# SmartHive_Client.net
KiCad netlist of a schematic drawn in Altium Designer
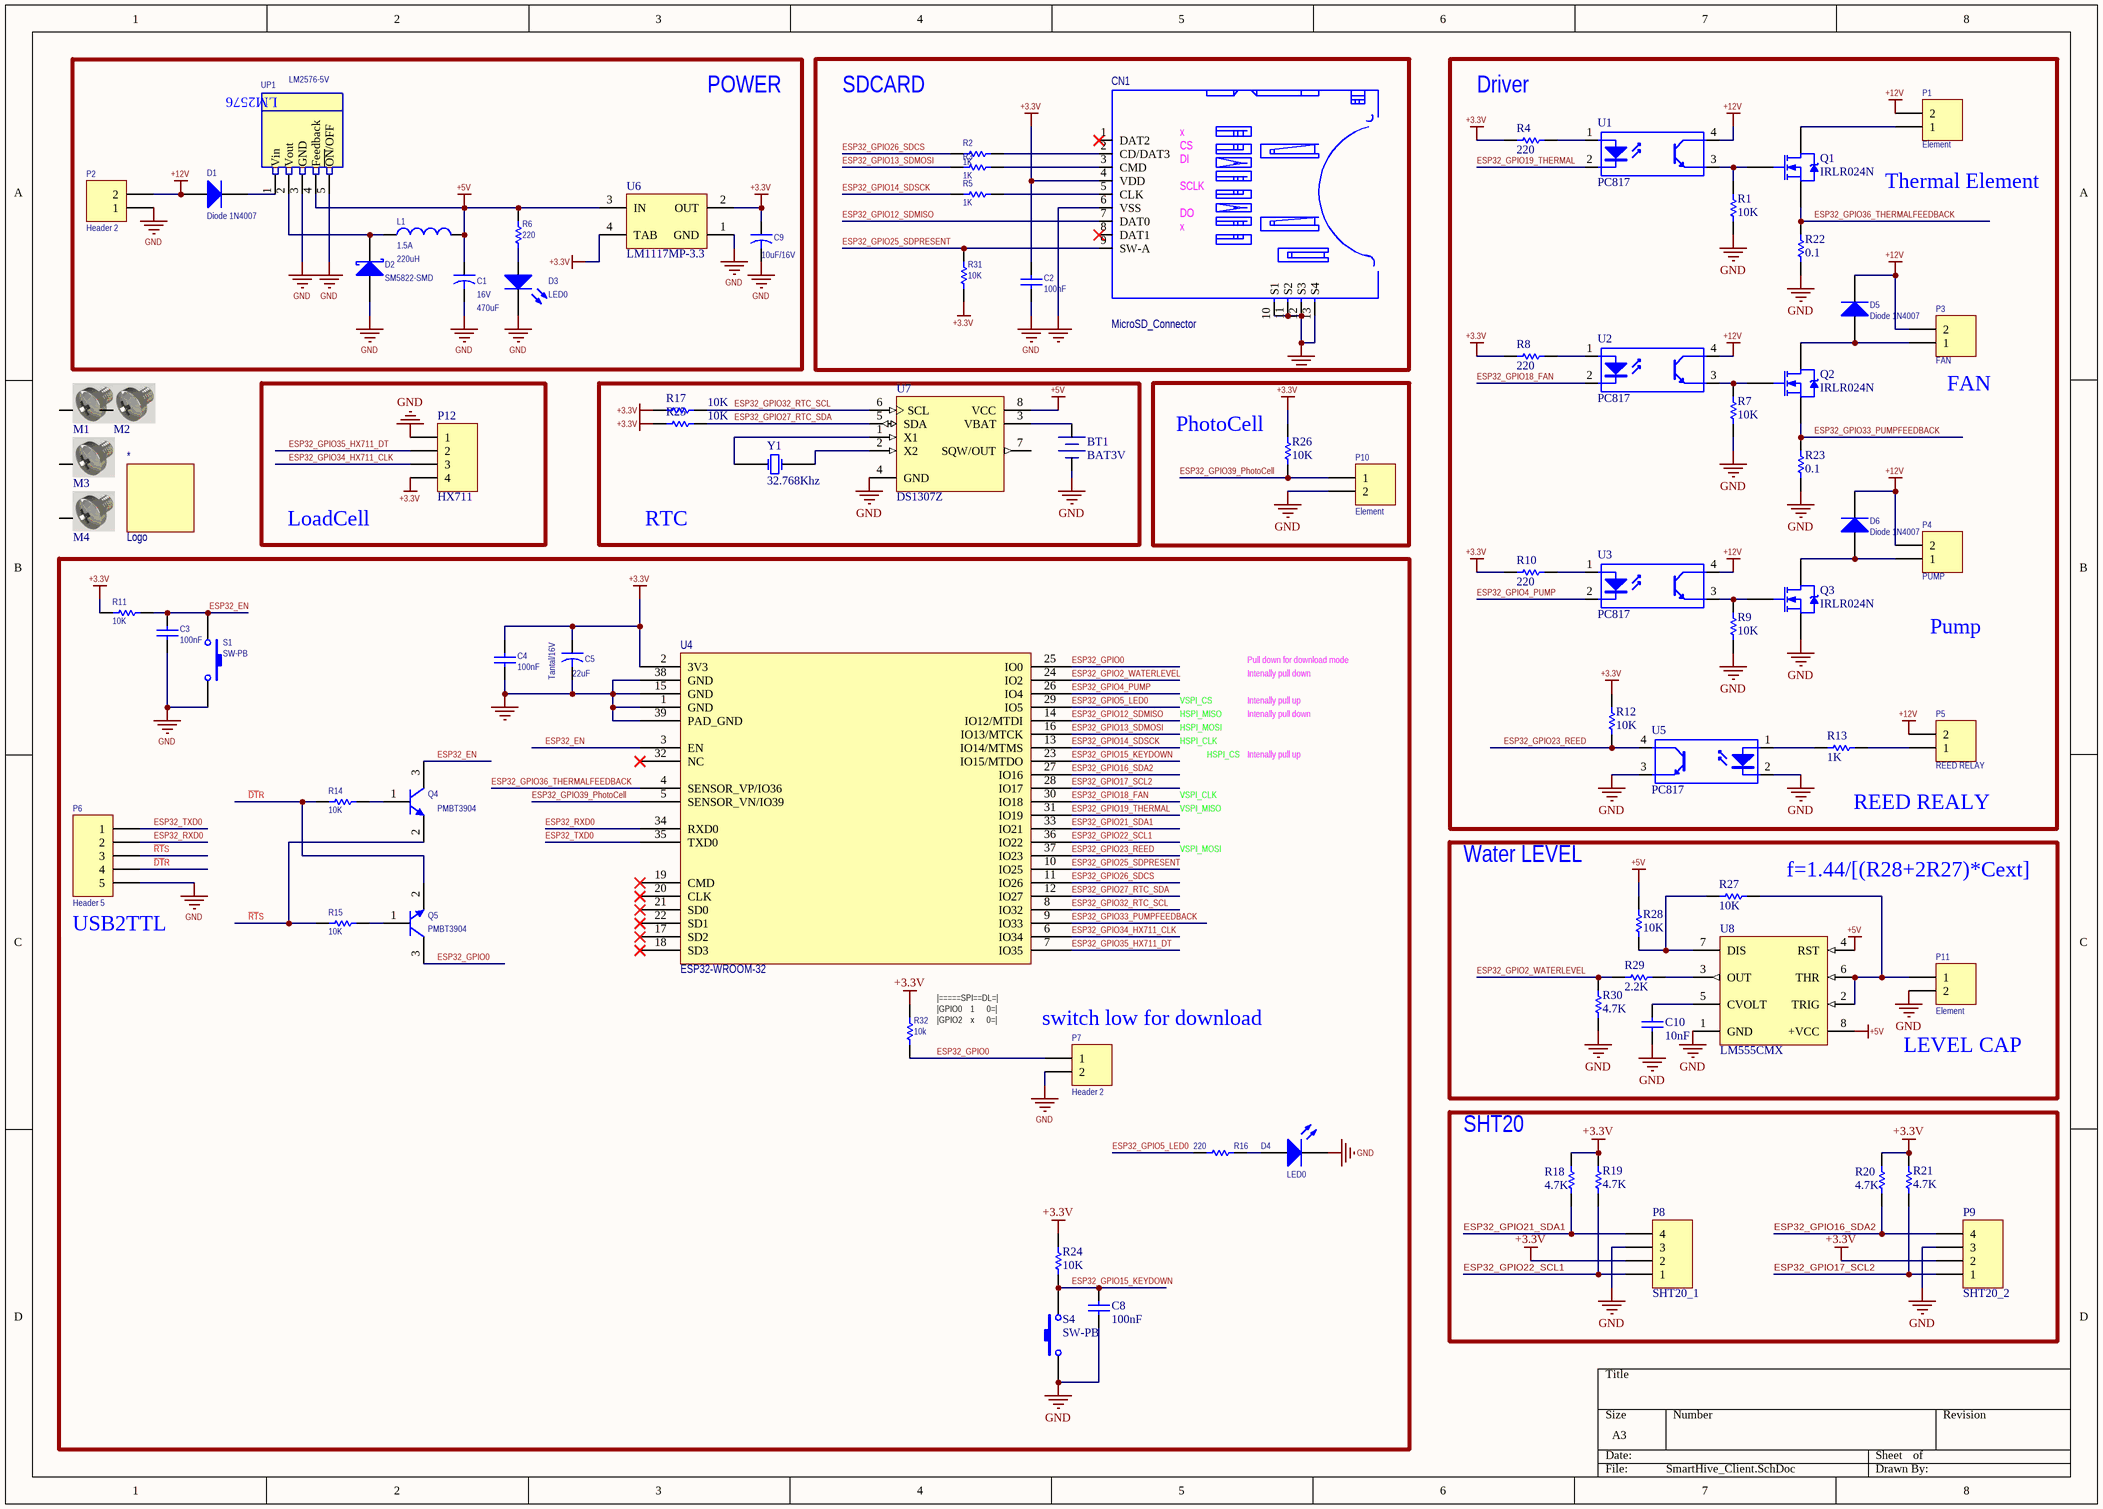
[diagram p0: SmartHive_Client.SchDoc]

(export (version "E")
  (design (tool "Eeschema 10.0.6"))
  (components
    (comp (ref "*") (value "Logo") (footprint "LOGO_PARS_TOP") (libsource (lib "Mofidi3D") (part "Logo")))
    (comp (ref "BT1")
      (value "BAT3V")
      (footprint "BTH2032_DIP")
      (description "Battry Backup")
      (fields (field (name "DESIGNER") "Abbas Basereh"))
      (libsource (lib "Mofidi3D") (part "Battry Backup"))
    )
    (comp (ref "C1")
      (value "16V")
      (footprint "Cap electrolitic radial 8x12-3.5")
      (description "Capacitor")
      (fields (field (name "ALTIUM_VALUE") "470uF") (field (name "PUBLISHER") "Altium Limited"))
      (libsource (lib "Miscellaneous Devices") (part "Cap2"))
    )
    (comp (ref "C2")
      (value "100nF")
      (footprint "CAP0805")
      (description "Capacitor")
      (fields (field (name "PUBLISHER") "Altium Limited"))
      (libsource (lib "Miscellaneous Devices") (part "Cap"))
    )
    (comp (ref "C3")
      (value "100nF")
      (footprint "CAP0805")
      (description "Capacitor")
      (fields (field (name "PUBLISHER") "Altium Limited"))
      (libsource (lib "Miscellaneous Devices") (part "Cap"))
    )
    (comp (ref "C4")
      (value "100nF")
      (footprint "CAP0805")
      (description "Capacitor")
      (fields (field (name "PUBLISHER") "Altium Limited"))
      (libsource (lib "Miscellaneous Devices") (part "Cap"))
    )
    (comp (ref "C5")
      (value "Tantal/16V")
      (footprint "CAP_TANTAL_TYPE_B")
      (description "Capacitor")
      (fields (field (name "ALTIUM_VALUE") "22uF") (field (name "PUBLISHER") "Altium Limited"))
      (libsource (lib "Miscellaneous Devices") (part "Cap2"))
    )
    (comp (ref "C8")
      (value "100nF")
      (footprint "CAP0805")
      (description "Capacitor")
      (fields (field (name "PUBLISHER") "Altium Limited"))
      (libsource (lib "Miscellaneous Devices") (part "Cap"))
    )
    (comp (ref "C9")
      (value "10uF/16V")
      (footprint "Cap electrolitic radial 5x11-2")
      (description "Capacitor")
      (fields (field (name "PUBLISHER") "Altium Limited"))
      (libsource (lib "Miscellaneous Devices") (part "Cap2"))
    )
    (comp (ref "C10")
      (value "10nF")
      (footprint "CAP0805")
      (description "Capacitor")
      (fields (field (name "PUBLISHER") "Altium Limited"))
      (libsource (lib "Miscellaneous Devices") (part "Cap"))
    )
    (comp (ref "CN1")
      (value "MicroSD_Connector")
      (footprint "MICRO_SD_TFP-09-2-12B")
      (libsource (lib "Mofidi3D") (part "MicroSD_Connector"))
    )
    (comp (ref "D1")
      (value "Diode 1N4007")
      (footprint "DO-241AC")
      (description "1 Amp General Purpose Rectifier")
      (fields (field (name "PUBLISHER") "Altium Limited"))
      (libsource (lib "Miscellaneous Devices") (part "Diode 1N4007"))
    )
    (comp (ref "D2")
      (value "SM5822-SMD")
      (footprint "430X270D")
      (description "Schottky Diode")
      (fields (field (name "PUBLISHER") "Altium Limited"))
      (libsource (lib "Miscellaneous Devices") (part "D Schottky"))
    )
    (comp (ref "D3")
      (value "LED0")
      (footprint "LED5MM_GRN")
      (description "Typical INFRARED GaAs LED")
      (fields (field (name "PUBLISHER") "Altium Limited"))
      (libsource (lib "Miscellaneous Devices") (part "LED0"))
    )
    (comp (ref "D4")
      (value "LED0")
      (footprint "LED5MM_BLUE")
      (description "Typical INFRARED GaAs LED")
      (fields (field (name "PUBLISHER") "Altium Limited"))
      (libsource (lib "Miscellaneous Devices") (part "LED0"))
    )
    (comp (ref "D5")
      (value "Diode 1N4007")
      (footprint "DO-241AC")
      (description "1 Amp General Purpose Rectifier")
      (fields (field (name "PUBLISHER") "Altium Limited"))
      (libsource (lib "Miscellaneous Devices") (part "Diode 1N4007"))
    )
    (comp (ref "D6")
      (value "Diode 1N4007")
      (footprint "DO-241AC")
      (description "1 Amp General Purpose Rectifier")
      (fields (field (name "PUBLISHER") "Altium Limited"))
      (libsource (lib "Miscellaneous Devices") (part "Diode 1N4007"))
    )
    (comp (ref "L1")
      (value "1.5A")
      (footprint "Inductor 10x12 (200 mils)")
      (description "Inductor")
      (fields (field (name "ALTIUM_VALUE") "220uH") (field (name "PUBLISHER") "Altium Limited"))
      (libsource (lib "Miscellaneous Devices") (part "Inductor"))
    )
    (comp (ref "M1")
      (value "Screw3mm")
      (footprint "Board Screw 3mm")
      (description "Board Screw With Spacer 3mm")
      (fields (field (name "DESIGNER") "Abbas Basereh"))
      (libsource (lib "Mofidi3D") (part "Board Screw 3mm"))
    )
    (comp (ref "M2")
      (value "Screw3mm")
      (footprint "Board Screw 3mm")
      (description "Board Screw With Spacer 3mm")
      (fields (field (name "DESIGNER") "Abbas Basereh"))
      (libsource (lib "Mofidi3D") (part "Board Screw 3mm"))
    )
    (comp (ref "M3")
      (value "Screw3mm")
      (footprint "Board Screw 3mm")
      (description "Board Screw With Spacer 3mm")
      (fields (field (name "DESIGNER") "Abbas Basereh"))
      (libsource (lib "Mofidi3D") (part "Board Screw 3mm"))
    )
    (comp (ref "M4")
      (value "Screw3mm")
      (footprint "Board Screw 3mm")
      (description "Board Screw With Spacer 3mm")
      (fields (field (name "DESIGNER") "Abbas Basereh"))
      (libsource (lib "Mofidi3D") (part "Board Screw 3mm"))
    )
    (comp (ref "P1")
      (value "Element")
      (footprint "MSTBV 2,5/2-G-5")
      (description "Header, 2-Pin")
      (fields (field (name "PUBLISHER") "Altium Limited"))
      (libsource (lib "") (part "Header 2_2"))
    )
    (comp (ref "P2")
      (value "Header 2")
      (footprint "MSTBV 2,5/2-G-5")
      (description "Header, 2-Pin")
      (fields (field (name "PUBLISHER") "Altium Limited"))
      (libsource (lib "") (part "Header 2_1"))
    )
    (comp (ref "P3")
      (value "FAN")
      (footprint "MSTBV 2,5/2-G-5")
      (description "Header, 2-Pin")
      (fields (field (name "PUBLISHER") "Altium Limited"))
      (libsource (lib "") (part "Header 2_2"))
    )
    (comp (ref "P4")
      (value "PUMP")
      (footprint "MSTBV 2,5/2-G-5")
      (description "Header, 2-Pin")
      (fields (field (name "PUBLISHER") "Altium Limited"))
      (libsource (lib "") (part "Header 2_2"))
    )
    (comp (ref "P5")
      (value "REED RELAY")
      (footprint "MSTBV 2,5/2-G-5")
      (description "Header, 2-Pin")
      (fields (field (name "PUBLISHER") "Altium Limited"))
      (libsource (lib "") (part "Header 2_2"))
    )
    (comp (ref "P6")
      (value "Header 5")
      (footprint "HDR1X5")
      (description "Header, 5-Pin")
      (fields (field (name "PUBLISHER") "Altium Limited"))
      (libsource (lib "Miscellaneous Connectors") (part "Header 5"))
    )
    (comp (ref "P7")
      (value "Header 2")
      (footprint "Jumper Small - 2.54 - Black")
      (description "Header, 2-Pin")
      (fields (field (name "PUBLISHER") "Altium Limited"))
      (libsource (lib "Miscellaneous Connectors") (part "Header 2"))
    )
    (comp (ref "P8")
      (value "SHT20_1")
      (footprint "XH-4PIN")
      (description "Header, 4-Pin")
      (fields (field (name "PUBLISHER") "Altium Limited"))
      (libsource (lib "Miscellaneous Connectors") (part "Header 4"))
    )
    (comp (ref "P9")
      (value "SHT20_2")
      (footprint "XH-4PIN")
      (description "Header, 4-Pin")
      (fields (field (name "PUBLISHER") "Altium Limited"))
      (libsource (lib "Miscellaneous Connectors") (part "Header 4"))
    )
    (comp (ref "P10")
      (value "Element")
      (footprint "DS1070-2-COMCON")
      (description "Header, 2-Pin")
      (fields (field (name "PUBLISHER") "Altium Limited"))
      (libsource (lib "Miscellaneous Connectors") (part "Header 2"))
    )
    (comp (ref "P11")
      (value "Element")
      (footprint "DS1070-2-COMCON")
      (description "Header, 2-Pin")
      (fields (field (name "PUBLISHER") "Altium Limited"))
      (libsource (lib "Miscellaneous Connectors") (part "Header 2"))
    )
    (comp (ref "P12")
      (value "HX711")
      (footprint "HDR1X4")
      (description "Header, 4-Pin")
      (fields (field (name "PUBLISHER") "Altium Limited"))
      (libsource (lib "") (part "Header 4_1"))
    )
    (comp (ref "Q1")
      (value "IRLR024N")
      (footprint "TO252-3M")
      (description "HEXFET Power MOSFET")
      (fields (field (name "PUBLISHER") "Altium Limited"))
      (libsource (lib "IR Discrete MOSFET - Power") (part "IRLR024N"))
    )
    (comp (ref "Q2")
      (value "IRLR024N")
      (footprint "TO252-3M")
      (description "HEXFET Power MOSFET")
      (fields (field (name "PUBLISHER") "Altium Limited"))
      (libsource (lib "IR Discrete MOSFET - Power") (part "IRLR024N"))
    )
    (comp (ref "Q3")
      (value "IRLR024N")
      (footprint "TO252-3M")
      (description "HEXFET Power MOSFET")
      (fields (field (name "PUBLISHER") "Altium Limited"))
      (libsource (lib "IR Discrete MOSFET - Power") (part "IRLR024N"))
    )
    (comp (ref "Q4")
      (value "PMBT3904")
      (footprint "Mofidi3D:SOT23_M")
      (description "NPN Switching Transistor")
      (fields (field (name "PUBLISHER") "Altium Limited"))
      (libsource (lib "Philips Discrete BJT - Low Power") (part "PMBT3904"))
    )
    (comp (ref "Q5")
      (value "PMBT3904")
      (footprint "Mofidi3D:SOT23_M")
      (description "NPN Switching Transistor")
      (fields (field (name "PUBLISHER") "Altium Limited"))
      (libsource (lib "Philips Discrete BJT - Low Power") (part "PMBT3904"))
    )
    (comp (ref "R1")
      (value "10K")
      (footprint "RES0805")
      (description "Resistor")
      (fields (field (name "PUBLISHER") "Altium Limited"))
      (libsource (lib "Miscellaneous Devices") (part "Res1"))
    )
    (comp (ref "R2")
      (value "1K")
      (footprint "RES0805")
      (description "Resistor")
      (fields (field (name "PUBLISHER") "Altium Limited"))
      (libsource (lib "Miscellaneous Devices") (part "Res1"))
    )
    (comp (ref "R3")
      (value "1K")
      (footprint "RES0805")
      (description "Resistor")
      (fields (field (name "PUBLISHER") "Altium Limited"))
      (libsource (lib "Miscellaneous Devices") (part "Res1"))
    )
    (comp (ref "R4")
      (value "220")
      (footprint "RES0805")
      (description "Resistor")
      (fields (field (name "PUBLISHER") "Altium Limited"))
      (libsource (lib "Miscellaneous Devices") (part "Res1"))
    )
    (comp (ref "R5")
      (value "1K")
      (footprint "RES0805")
      (description "Resistor")
      (fields (field (name "PUBLISHER") "Altium Limited"))
      (libsource (lib "Miscellaneous Devices") (part "Res1"))
    )
    (comp (ref "R6")
      (value "220")
      (footprint "RES0805")
      (description "Resistor")
      (fields (field (name "PUBLISHER") "Altium Limited"))
      (libsource (lib "Miscellaneous Devices") (part "Res1"))
    )
    (comp (ref "R7")
      (value "10K")
      (footprint "RES0805")
      (description "Resistor")
      (fields (field (name "PUBLISHER") "Altium Limited"))
      (libsource (lib "Miscellaneous Devices") (part "Res1"))
    )
    (comp (ref "R8")
      (value "220")
      (footprint "RES0805")
      (description "Resistor")
      (fields (field (name "PUBLISHER") "Altium Limited"))
      (libsource (lib "Miscellaneous Devices") (part "Res1"))
    )
    (comp (ref "R9")
      (value "10K")
      (footprint "RES0805")
      (description "Resistor")
      (fields (field (name "PUBLISHER") "Altium Limited"))
      (libsource (lib "Miscellaneous Devices") (part "Res1"))
    )
    (comp (ref "R10")
      (value "220")
      (footprint "RES0805")
      (description "Resistor")
      (fields (field (name "PUBLISHER") "Altium Limited"))
      (libsource (lib "Miscellaneous Devices") (part "Res1"))
    )
    (comp (ref "R11")
      (value "10K")
      (footprint "RES0805")
      (description "Resistor")
      (fields (field (name "PUBLISHER") "Altium Limited"))
      (libsource (lib "Miscellaneous Devices") (part "Res1"))
    )
    (comp (ref "R12")
      (value "10K")
      (footprint "RES0805")
      (description "Resistor")
      (fields (field (name "PUBLISHER") "Altium Limited"))
      (libsource (lib "Miscellaneous Devices") (part "Res1"))
    )
    (comp (ref "R13")
      (value "1K")
      (footprint "RES0805")
      (description "Resistor")
      (fields (field (name "PUBLISHER") "Altium Limited"))
      (libsource (lib "Miscellaneous Devices") (part "Res1"))
    )
    (comp (ref "R14")
      (value "10K")
      (footprint "RES0805")
      (description "Resistor")
      (fields (field (name "PUBLISHER") "Altium Limited"))
      (libsource (lib "Miscellaneous Devices") (part "Res1"))
    )
    (comp (ref "R15")
      (value "10K")
      (footprint "RES0805")
      (description "Resistor")
      (fields (field (name "PUBLISHER") "Altium Limited"))
      (libsource (lib "Miscellaneous Devices") (part "Res1"))
    )
    (comp (ref "R16")
      (value "220")
      (footprint "RES0805")
      (description "Resistor")
      (fields (field (name "PUBLISHER") "Altium Limited"))
      (libsource (lib "Miscellaneous Devices") (part "Res1"))
    )
    (comp (ref "R17")
      (value "10K")
      (footprint "RES0805")
      (description "Resistor")
      (fields (field (name "PUBLISHER") "Altium Limited"))
      (libsource (lib "Miscellaneous Devices") (part "Res1"))
    )
    (comp (ref "R18")
      (value "4.7K")
      (footprint "RES0805")
      (description "Resistor")
      (fields (field (name "PUBLISHER") "Altium Limited"))
      (libsource (lib "Miscellaneous Devices") (part "Res1"))
    )
    (comp (ref "R19")
      (value "4.7K")
      (footprint "RES0805")
      (description "Resistor")
      (fields (field (name "PUBLISHER") "Altium Limited"))
      (libsource (lib "Miscellaneous Devices") (part "Res1"))
    )
    (comp (ref "R20")
      (value "4.7K")
      (footprint "RES0805")
      (description "Resistor")
      (fields (field (name "PUBLISHER") "Altium Limited"))
      (libsource (lib "Miscellaneous Devices") (part "Res1"))
    )
    (comp (ref "R21")
      (value "4.7K")
      (footprint "RES0805")
      (description "Resistor")
      (fields (field (name "PUBLISHER") "Altium Limited"))
      (libsource (lib "Miscellaneous Devices") (part "Res1"))
    )
    (comp (ref "R22")
      (value "0.1")
      (footprint "RES2512")
      (description "Size:2512,1%")
      (fields (field (name "PUBLISHER") "Altium Limited"))
      (libsource (lib "Miscellaneous Devices") (part "Res1"))
    )
    (comp (ref "R23")
      (value "0.1")
      (footprint "RES2512")
      (description "Size:2512,1%")
      (fields (field (name "PUBLISHER") "Altium Limited"))
      (libsource (lib "Miscellaneous Devices") (part "Res1"))
    )
    (comp (ref "R24")
      (value "10K")
      (footprint "RES0805")
      (description "Resistor")
      (fields (field (name "PUBLISHER") "Altium Limited"))
      (libsource (lib "Miscellaneous Devices") (part "Res1"))
    )
    (comp (ref "R25")
      (value "10K")
      (footprint "RES0805")
      (description "Resistor")
      (fields (field (name "PUBLISHER") "Altium Limited"))
      (libsource (lib "Miscellaneous Devices") (part "Res1"))
    )
    (comp (ref "R26")
      (value "10K")
      (footprint "RES0805")
      (description "Resistor")
      (fields (field (name "PUBLISHER") "Altium Limited"))
      (libsource (lib "Miscellaneous Devices") (part "Res1"))
    )
    (comp (ref "R27")
      (value "10K")
      (footprint "RES0805")
      (description "Resistor")
      (fields (field (name "PUBLISHER") "Altium Limited"))
      (libsource (lib "Miscellaneous Devices") (part "Res1"))
    )
    (comp (ref "R28")
      (value "10K")
      (footprint "RES0805")
      (description "Resistor")
      (fields (field (name "PUBLISHER") "Altium Limited"))
      (libsource (lib "Miscellaneous Devices") (part "Res1"))
    )
    (comp (ref "R29")
      (value "2.2K")
      (footprint "RES0805")
      (description "Resistor")
      (fields (field (name "PUBLISHER") "Altium Limited"))
      (libsource (lib "Miscellaneous Devices") (part "Res1"))
    )
    (comp (ref "R30")
      (value "4.7K")
      (footprint "RES0805")
      (description "Resistor")
      (fields (field (name "PUBLISHER") "Altium Limited"))
      (libsource (lib "Miscellaneous Devices") (part "Res1"))
    )
    (comp (ref "R31")
      (value "10K")
      (footprint "RES0805")
      (description "Resistor")
      (fields (field (name "PUBLISHER") "Altium Limited"))
      (libsource (lib "Miscellaneous Devices") (part "Res1"))
    )
    (comp (ref "R32")
      (value "10k")
      (footprint "RES0805")
      (description "Resistor")
      (fields (field (name "PUBLISHER") "Altium Limited"))
      (libsource (lib "Miscellaneous Devices") (part "Res1"))
    )
    (comp (ref "S1")
      (value "SW-PB")
      (footprint "SW-2PIN-SMD")
      (description "Switch")
      (fields (field (name "PUBLISHER") "Altium Limited"))
      (libsource (lib "Miscellaneous Devices") (part "SW-PB"))
    )
    (comp (ref "S4")
      (value "SW-PB")
      (footprint "SW-4PIN")
      (description "Switch")
      (fields (field (name "PUBLISHER") "Altium Limited"))
      (libsource (lib "Miscellaneous Devices") (part "SW-PB"))
    )
    (comp (ref "U1")
      (value "PC817")
      (footprint "DIP_4")
      (description "4-Pin Phototransistor Optocoupler")
      (fields (field (name "PUBLISHER") "Altium Limited"))
      (libsource (lib "Miscellaneous Devices") (part "Optoisolator1"))
    )
    (comp (ref "U2")
      (value "PC817")
      (footprint "DIP_4")
      (description "4-Pin Phototransistor Optocoupler")
      (fields (field (name "PUBLISHER") "Altium Limited"))
      (libsource (lib "Miscellaneous Devices") (part "Optoisolator1"))
    )
    (comp (ref "U3")
      (value "PC817")
      (footprint "DIP_4")
      (description "4-Pin Phototransistor Optocoupler")
      (fields (field (name "PUBLISHER") "Altium Limited"))
      (libsource (lib "Miscellaneous Devices") (part "Optoisolator1"))
    )
    (comp (ref "U4")
      (value "ESP32-WROOM-32")
      (footprint "ESP32-WROOM-32D")
      (description "ESP32  a single chip 2.4 GHz Wi-Fi and Bluetooth combo chip")
      (libsource (lib "Mofidi3D") (part "ESP32-WROOM-32"))
    )
    (comp (ref "U5")
      (value "PC817")
      (footprint "DIP_4")
      (description "4-Pin Phototransistor Optocoupler")
      (fields (field (name "PUBLISHER") "Altium Limited"))
      (libsource (lib "Miscellaneous Devices") (part "Optoisolator1"))
    )
    (comp (ref "U6")
      (value "LM1117MP-3.3")
      (footprint "SOT223_4")
      (description "800mA Low-Dropout Linear Regulator, 4-pin SOT-223")
      (fields
        (field (name "MANUFACTURER") "National Semiconductor")
        (field (name "PUBLISHER") "Altium Limited")
      )
      (libsource (lib "NSC LDO") (part "LM1117MP-3.3"))
    )
    (comp (ref "U7")
      (value "DS1307Z")
      (footprint "SO-8N")
      (description "64 X 8 Serial Real-Time Clock")
      (fields (field (name "PUBLISHER") "Altium Limited"))
      (libsource (lib "Dallas Peripheral Real Time Clock") (part "DS1307Z"))
    )
    (comp (ref "U8")
      (value "LM555CMX")
      (footprint "SO-8N")
      (description "Timer, 8-pin Narrow SOIC")
      (fields
        (field (name "MANUFACTURER") "National Semiconductor")
        (field (name "PUBLISHER") "Altium Limited")
      )
      (libsource (lib "NSC Analog") (part "LM555CMX"))
    )
    (comp (ref "UP1")
      (value "LM2576-5V")
      (footprint "TO-220_5 with heatsink HS sot32")
      (description "3.3V, 3A variable output step-down switching voltage regulator")
      (fields (field (name "DESIGNER") "Abbas Basereh"))
      (libsource (lib "Mofidi3D") (part "LM2576-Adj"))
    )
    (comp (ref "Y1")
      (value "32.768Khz")
      (footprint "Crystal_NC308")
      (description "XTAL Crystal")
      (fields (field (name "DESIGNER") "ABBAS BASEREH"))
      (libsource (lib "Mofidi3D") (part "XTAL_Crystal"))
    )
  )
  (nets
    (net (code "1") (name "+3.3V") (class "Default")
      (node (ref "C2") (pin "2") (pinfunction "2_2") (pintype "passive"))
      (node (ref "C4") (pin "2") (pinfunction "2_2") (pintype "passive"))
      (node (ref "C5") (pin "1") (pinfunction "1_1") (pintype "passive"))
      (node (ref "C9") (pin "1") (pinfunction "1_1") (pintype "passive"))
      (node (ref "CN1") (pin "4") (pinfunction "VDD_4") (pintype "passive"))
      (node (ref "P12") (pin "4") (pinfunction "4_4") (pintype "passive"))
      (node (ref "P8") (pin "2") (pinfunction "2_2") (pintype "passive"))
      (node (ref "P9") (pin "2") (pinfunction "2_2") (pintype "passive"))
      (node (ref "R10") (pin "1") (pinfunction "1_1") (pintype "passive"))
      (node (ref "R11") (pin "2") (pinfunction "2_2") (pintype "passive"))
      (node (ref "R12") (pin "2") (pinfunction "2_2") (pintype "passive"))
      (node (ref "R17") (pin "2") (pinfunction "2_2") (pintype "passive"))
      (node (ref "R18") (pin "2") (pinfunction "2_2") (pintype "passive"))
      (node (ref "R19") (pin "2") (pinfunction "2_2") (pintype "passive"))
      (node (ref "R20") (pin "2") (pinfunction "2_2") (pintype "passive"))
      (node (ref "R21") (pin "2") (pinfunction "2_2") (pintype "passive"))
      (node (ref "R24") (pin "2") (pinfunction "2_2") (pintype "passive"))
      (node (ref "R25") (pin "2") (pinfunction "2_2") (pintype "passive"))
      (node (ref "R26") (pin "2") (pinfunction "2_2") (pintype "passive"))
      (node (ref "R31") (pin "2") (pinfunction "2_2") (pintype "passive"))
      (node (ref "R32") (pin "2") (pinfunction "2_2") (pintype "passive"))
      (node (ref "R4") (pin "1") (pinfunction "1_1") (pintype "passive"))
      (node (ref "R8") (pin "1") (pinfunction "1_1") (pintype "passive"))
      (node (ref "U4") (pin "2") (pinfunction "3V3_2") (pintype "power_in"))
      (node (ref "U6") (pin "2") (pinfunction "OUT_2") (pintype "power_in"))
      (node (ref "U6") (pin "4") (pinfunction "TAB_4") (pintype "power_in"))
    )
    (net (code "2") (name "+5V") (class "Default")
      (node (ref "C1") (pin "1") (pinfunction "1_1") (pintype "passive"))
      (node (ref "L1") (pin "2") (pinfunction "2_2") (pintype "passive"))
      (node (ref "R28") (pin "2") (pinfunction "2_2") (pintype "passive"))
      (node (ref "R6") (pin "2") (pinfunction "2_2") (pintype "passive"))
      (node (ref "U6") (pin "3") (pinfunction "IN_3") (pintype "power_in"))
      (node (ref "U7") (pin "8") (pinfunction "VCC_8") (pintype "power_in"))
      (node (ref "U8") (pin "4") (pinfunction "RST_4") (pintype "input"))
      (node (ref "U8") (pin "8") (pinfunction "+VCC_8") (pintype "power_in"))
      (node (ref "UP1") (pin "4") (pinfunction "Feedback_4") (pintype "passive"))
    )
    (net (code "3") (name "+12V") (class "Default")
      (node (ref "D1") (pin "1") (pinfunction "A_1") (pintype "passive"))
      (node (ref "D5") (pin "2") (pinfunction "K_2") (pintype "passive"))
      (node (ref "D6") (pin "2") (pinfunction "K_2") (pintype "passive"))
      (node (ref "P1") (pin "2") (pinfunction "2_2") (pintype "passive"))
      (node (ref "P2") (pin "2") (pinfunction "2_2") (pintype "passive"))
      (node (ref "P3") (pin "2") (pinfunction "2_2") (pintype "passive"))
      (node (ref "P4") (pin "2") (pinfunction "2_2") (pintype "passive"))
      (node (ref "P5") (pin "2") (pinfunction "2_2") (pintype "passive"))
      (node (ref "U1") (pin "4") (pinfunction "C_4") (pintype "passive"))
      (node (ref "U2") (pin "4") (pinfunction "C_4") (pintype "passive"))
      (node (ref "U3") (pin "4") (pinfunction "C_4") (pintype "passive"))
    )
    (net (code "4") (name "/ESP32_EN") (class "Default")
      (node (ref "C3") (pin "2") (pinfunction "2_2") (pintype "passive"))
      (node (ref "Q4") (pin "3") (pinfunction "C_3") (pintype "passive"))
      (node (ref "R11") (pin "1") (pinfunction "1_1") (pintype "passive"))
      (node (ref "S1") (pin "1") (pinfunction "1_1") (pintype "passive"))
      (node (ref "U4") (pin "3") (pinfunction "EN_3") (pintype "passive"))
    )
    (net (code "5") (name "/ESP32_GPIO0") (class "Default")
      (node (ref "P7") (pin "1") (pinfunction "1_1") (pintype "passive"))
      (node (ref "Q5") (pin "3") (pinfunction "C_3") (pintype "passive"))
      (node (ref "R32") (pin "1") (pinfunction "1_1") (pintype "passive"))
      (node (ref "U4") (pin "25") (pinfunction "IO0_25") (pintype "passive"))
    )
    (net (code "6") (name "/ESP32_GPIO2_WATERLEVEL") (class "Default")
      (node (ref "R29") (pin "2") (pinfunction "2_2") (pintype "passive"))
      (node (ref "R30") (pin "2") (pinfunction "2_2") (pintype "passive"))
      (node (ref "U4") (pin "24") (pinfunction "IO2_24") (pintype "passive"))
    )
    (net (code "7") (name "/ESP32_GPIO4_PUMP") (class "Default")
      (node (ref "U3") (pin "2") (pinfunction "K_2") (pintype "passive"))
      (node (ref "U4") (pin "26") (pinfunction "IO4_26") (pintype "passive"))
    )
    (net (code "8") (name "/ESP32_GPIO5_LED0") (class "Default")
      (node (ref "R16") (pin "1") (pinfunction "1_1") (pintype "passive"))
      (node (ref "U4") (pin "29") (pinfunction "IO5_29") (pintype "passive"))
    )
    (net (code "9") (name "/ESP32_GPIO12_SDMISO") (class "Default")
      (node (ref "CN1") (pin "7") (pinfunction "DAT0_7") (pintype "passive"))
      (node (ref "U4") (pin "14") (pinfunction "IO12/MTDI_14") (pintype "passive"))
    )
    (net (code "10") (name "/ESP32_GPIO13_SDMOSI") (class "Default")
      (node (ref "R3") (pin "2") (pinfunction "2_2") (pintype "passive"))
      (node (ref "U4") (pin "16") (pinfunction "IO13/MTCK_16") (pintype "passive"))
    )
    (net (code "11") (name "/ESP32_GPIO14_SDSCK") (class "Default")
      (node (ref "R5") (pin "2") (pinfunction "2_2") (pintype "passive"))
      (node (ref "U4") (pin "13") (pinfunction "IO14/MTMS_13") (pintype "passive"))
    )
    (net (code "12") (name "/ESP32_GPIO15_KEYDOWN") (class "Default")
      (node (ref "C8") (pin "2") (pinfunction "2_2") (pintype "passive"))
      (node (ref "R24") (pin "1") (pinfunction "1_1") (pintype "passive"))
      (node (ref "S4") (pin "1") (pinfunction "1_1") (pintype "passive"))
      (node (ref "U4") (pin "23") (pinfunction "IO15/MTDO_23") (pintype "passive"))
    )
    (net (code "13") (name "/ESP32_GPIO16_SDA2") (class "Default")
      (node (ref "P9") (pin "4") (pinfunction "4_4") (pintype "passive"))
      (node (ref "R20") (pin "1") (pinfunction "1_1") (pintype "passive"))
      (node (ref "U4") (pin "27") (pinfunction "IO16_27") (pintype "passive"))
    )
    (net (code "14") (name "/ESP32_GPIO17_SCL2") (class "Default")
      (node (ref "P9") (pin "1") (pinfunction "1_1") (pintype "passive"))
      (node (ref "R21") (pin "1") (pinfunction "1_1") (pintype "passive"))
      (node (ref "U4") (pin "28") (pinfunction "IO17_28") (pintype "passive"))
    )
    (net (code "15") (name "/ESP32_GPIO18_FAN") (class "Default")
      (node (ref "U2") (pin "2") (pinfunction "K_2") (pintype "passive"))
      (node (ref "U4") (pin "30") (pinfunction "IO18_30") (pintype "passive"))
    )
    (net (code "16") (name "/ESP32_GPIO19_THERMAL") (class "Default")
      (node (ref "U1") (pin "2") (pinfunction "K_2") (pintype "passive"))
      (node (ref "U4") (pin "31") (pinfunction "IO19_31") (pintype "passive"))
    )
    (net (code "17") (name "/ESP32_GPIO21_SDA1") (class "Default")
      (node (ref "P8") (pin "4") (pinfunction "4_4") (pintype "passive"))
      (node (ref "R18") (pin "1") (pinfunction "1_1") (pintype "passive"))
      (node (ref "U4") (pin "33") (pinfunction "IO21_33") (pintype "passive"))
    )
    (net (code "18") (name "/ESP32_GPIO22_SCL1") (class "Default")
      (node (ref "P8") (pin "1") (pinfunction "1_1") (pintype "passive"))
      (node (ref "R19") (pin "1") (pinfunction "1_1") (pintype "passive"))
      (node (ref "U4") (pin "36") (pinfunction "IO22_36") (pintype "passive"))
    )
    (net (code "19") (name "/ESP32_GPIO23_REED") (class "Default")
      (node (ref "R12") (pin "1") (pinfunction "1_1") (pintype "passive"))
      (node (ref "U4") (pin "37") (pinfunction "IO23_37") (pintype "passive"))
      (node (ref "U5") (pin "4") (pinfunction "C_4") (pintype "passive"))
    )
    (net (code "20") (name "/ESP32_GPIO25_SDPRESENT") (class "Default")
      (node (ref "CN1") (pin "9") (pinfunction "SW-A_9") (pintype "passive"))
      (node (ref "R31") (pin "1") (pinfunction "1_1") (pintype "passive"))
      (node (ref "U4") (pin "10") (pinfunction "IO25_10") (pintype "passive"))
    )
    (net (code "21") (name "/ESP32_GPIO26_SDCS") (class "Default")
      (node (ref "R2") (pin "2") (pinfunction "2_2") (pintype "passive"))
      (node (ref "U4") (pin "11") (pinfunction "IO26_11") (pintype "passive"))
    )
    (net (code "22") (name "/ESP32_GPIO27_RTC_SDA") (class "Default")
      (node (ref "R25") (pin "1") (pinfunction "1_1") (pintype "passive"))
      (node (ref "U4") (pin "12") (pinfunction "IO27_12") (pintype "passive"))
      (node (ref "U7") (pin "5") (pinfunction "SDA_5") (pintype "bidirectional"))
    )
    (net (code "23") (name "/ESP32_GPIO32_RTC_SCL") (class "Default")
      (node (ref "R17") (pin "1") (pinfunction "1_1") (pintype "passive"))
      (node (ref "U4") (pin "8") (pinfunction "IO32_8") (pintype "passive"))
      (node (ref "U7") (pin "6") (pinfunction "SCL_6") (pintype "input"))
    )
    (net (code "24") (name "/ESP32_GPIO33_PUMPFEEDBACK") (class "Default")
      (node (ref "Q2") (pin "3") (pinfunction "S_3") (pintype "passive"))
      (node (ref "R23") (pin "2") (pinfunction "2_2") (pintype "passive"))
      (node (ref "U4") (pin "9") (pinfunction "IO33_9") (pintype "passive"))
    )
    (net (code "25") (name "/ESP32_GPIO34_HX711_CLK") (class "Default")
      (node (ref "P12") (pin "3") (pinfunction "3_3") (pintype "passive"))
      (node (ref "U4") (pin "6") (pinfunction "IO34_6") (pintype "passive"))
    )
    (net (code "26") (name "/ESP32_GPIO35_HX711_DT") (class "Default")
      (node (ref "P12") (pin "2") (pinfunction "2_2") (pintype "passive"))
      (node (ref "U4") (pin "7") (pinfunction "IO35_7") (pintype "passive"))
    )
    (net (code "27") (name "/ESP32_GPIO36_THERMALFEEDBACK") (class "Default")
      (node (ref "Q1") (pin "3") (pinfunction "S_3") (pintype "passive"))
      (node (ref "R22") (pin "2") (pinfunction "2_2") (pintype "passive"))
      (node (ref "U4") (pin "4") (pinfunction "SENSOR_VP/IO36_4") (pintype "passive"))
    )
    (net (code "28") (name "/ESP32_GPIO39_PhotoCell") (class "Default")
      (node (ref "P10") (pin "1") (pinfunction "1_1") (pintype "passive"))
      (node (ref "R26") (pin "1") (pinfunction "1_1") (pintype "passive"))
      (node (ref "U4") (pin "5") (pinfunction "SENSOR_VN/IO39_5") (pintype "passive"))
    )
    (net (code "29") (name "/ESP32_RXD0") (class "Default")
      (node (ref "P6") (pin "2") (pinfunction "2_2") (pintype "passive"))
      (node (ref "U4") (pin "34") (pinfunction "RXD0_34") (pintype "passive"))
    )
    (net (code "30") (name "/ESP32_TXD0") (class "Default")
      (node (ref "P6") (pin "1") (pinfunction "1_1") (pintype "passive"))
      (node (ref "U4") (pin "35") (pinfunction "TXD0_35") (pintype "passive"))
    )
    (net (code "31") (name "/~{DT}R") (class "Default")
      (node (ref "P6") (pin "4") (pinfunction "4_4") (pintype "passive"))
      (node (ref "Q5") (pin "2") (pinfunction "E_2") (pintype "passive"))
      (node (ref "R14") (pin "2") (pinfunction "2_2") (pintype "passive"))
    )
    (net (code "32") (name "/~{RT}S") (class "Default")
      (node (ref "P6") (pin "3") (pinfunction "3_3") (pintype "passive"))
      (node (ref "Q4") (pin "2") (pinfunction "E_2") (pintype "passive"))
      (node (ref "R15") (pin "2") (pinfunction "2_2") (pintype "passive"))
    )
    (net (code "33") (name "GND") (class "Default")
      (node (ref "BT1") (pin "2") (pinfunction "-_2") (pintype "passive"))
      (node (ref "C1") (pin "2") (pinfunction "2_2") (pintype "passive"))
      (node (ref "C10") (pin "1") (pinfunction "1_1") (pintype "passive"))
      (node (ref "C2") (pin "1") (pinfunction "1_1") (pintype "passive"))
      (node (ref "C3") (pin "1") (pinfunction "1_1") (pintype "passive"))
      (node (ref "C4") (pin "1") (pinfunction "1_1") (pintype "passive"))
      (node (ref "C5") (pin "2") (pinfunction "2_2") (pintype "passive"))
      (node (ref "C8") (pin "1") (pinfunction "1_1") (pintype "passive"))
      (node (ref "C9") (pin "2") (pinfunction "2_2") (pintype "passive"))
      (node (ref "CN1") (pin "10") (pinfunction "S1_10") (pintype "passive"))
      (node (ref "CN1") (pin "11") (pinfunction "S2_11") (pintype "passive"))
      (node (ref "CN1") (pin "12") (pinfunction "S3_12") (pintype "passive"))
      (node (ref "CN1") (pin "13") (pinfunction "S4_13") (pintype "passive"))
      (node (ref "CN1") (pin "6") (pinfunction "VSS_6") (pintype "passive"))
      (node (ref "D2") (pin "1") (pinfunction "A_1") (pintype "passive"))
      (node (ref "D3") (pin "2") (pinfunction "K_2") (pintype "passive"))
      (node (ref "D4") (pin "2") (pinfunction "K_2") (pintype "passive"))
      (node (ref "P10") (pin "2") (pinfunction "2_2") (pintype "passive"))
      (node (ref "P11") (pin "2") (pinfunction "2_2") (pintype "passive"))
      (node (ref "P12") (pin "1") (pinfunction "1_1") (pintype "passive"))
      (node (ref "P2") (pin "1") (pinfunction "1_1") (pintype "passive"))
      (node (ref "P6") (pin "5") (pinfunction "5_5") (pintype "passive"))
      (node (ref "P7") (pin "2") (pinfunction "2_2") (pintype "passive"))
      (node (ref "P8") (pin "3") (pinfunction "3_3") (pintype "passive"))
      (node (ref "P9") (pin "3") (pinfunction "3_3") (pintype "passive"))
      (node (ref "Q3") (pin "3") (pinfunction "S_3") (pintype "passive"))
      (node (ref "R1") (pin "1") (pinfunction "1_1") (pintype "passive"))
      (node (ref "R22") (pin "1") (pinfunction "1_1") (pintype "passive"))
      (node (ref "R23") (pin "1") (pinfunction "1_1") (pintype "passive"))
      (node (ref "R30") (pin "1") (pinfunction "1_1") (pintype "passive"))
      (node (ref "R7") (pin "1") (pinfunction "1_1") (pintype "passive"))
      (node (ref "R9") (pin "1") (pinfunction "1_1") (pintype "passive"))
      (node (ref "S1") (pin "2") (pinfunction "2_2") (pintype "passive"))
      (node (ref "S4") (pin "2") (pinfunction "2_2") (pintype "passive"))
      (node (ref "U4") (pin "1") (pinfunction "GND_1") (pintype "power_in"))
      (node (ref "U4") (pin "15") (pinfunction "GND_15") (pintype "power_in"))
      (node (ref "U4") (pin "38") (pinfunction "GND_38") (pintype "power_in"))
      (node (ref "U4") (pin "39") (pinfunction "PAD_GND_39") (pintype "passive"))
      (node (ref "U5") (pin "2") (pinfunction "K_2") (pintype "passive"))
      (node (ref "U5") (pin "3") (pinfunction "E_3") (pintype "passive"))
      (node (ref "U6") (pin "1") (pinfunction "GND_1") (pintype "power_in"))
      (node (ref "U7") (pin "4") (pinfunction "GND_4") (pintype "power_in"))
      (node (ref "U8") (pin "1") (pinfunction "GND_1") (pintype "power_in"))
      (node (ref "UP1") (pin "3") (pinfunction "GND_3") (pintype "passive"))
      (node (ref "UP1") (pin "5") (pinfunction "~{ON}/OFF_5") (pintype "passive"))
    )
    (net (code "34") (name "Net-(BT1-+)") (class "Default")
      (node (ref "BT1") (pin "1") (pinfunction "+_1") (pintype "passive"))
      (node (ref "U7") (pin "3") (pinfunction "VBAT_3") (pintype "power_in"))
    )
    (net (code "35") (name "Net-(CN1-CD{slash}DAT3)") (class "Default")
      (node (ref "CN1") (pin "2") (pinfunction "CD/DAT3_2") (pintype "passive"))
      (node (ref "R2") (pin "1") (pinfunction "1_1") (pintype "passive"))
    )
    (net (code "36") (name "Net-(CN1-CLK)") (class "Default")
      (node (ref "CN1") (pin "5") (pinfunction "CLK_5") (pintype "passive"))
      (node (ref "R5") (pin "1") (pinfunction "1_1") (pintype "passive"))
    )
    (net (code "37") (name "Net-(CN1-CMD)") (class "Default")
      (node (ref "CN1") (pin "3") (pinfunction "CMD_3") (pintype "passive"))
      (node (ref "R3") (pin "1") (pinfunction "1_1") (pintype "passive"))
    )
    (net (code "38") (name "Net-(D1-K)") (class "Default")
      (node (ref "D1") (pin "2") (pinfunction "K_2") (pintype "passive"))
      (node (ref "UP1") (pin "1") (pinfunction "Vin_1") (pintype "passive"))
    )
    (net (code "39") (name "Net-(D2-K)") (class "Default")
      (node (ref "D2") (pin "2") (pinfunction "K_2") (pintype "passive"))
      (node (ref "L1") (pin "1") (pinfunction "1_1") (pintype "passive"))
      (node (ref "UP1") (pin "2") (pinfunction "Vout_2") (pintype "passive"))
    )
    (net (code "40") (name "Net-(D3-A)") (class "Default")
      (node (ref "D3") (pin "1") (pinfunction "A_1") (pintype "passive"))
      (node (ref "R6") (pin "1") (pinfunction "1_1") (pintype "passive"))
    )
    (net (code "41") (name "Net-(D4-A)") (class "Default")
      (node (ref "D4") (pin "1") (pinfunction "A_1") (pintype "passive"))
      (node (ref "R16") (pin "2") (pinfunction "2_2") (pintype "passive"))
    )
    (net (code "42") (name "Net-(D5-A)") (class "Default")
      (node (ref "D5") (pin "1") (pinfunction "A_1") (pintype "passive"))
      (node (ref "P3") (pin "1") (pinfunction "1_1") (pintype "passive"))
      (node (ref "Q2") (pin "4") (pinfunction "D_4") (pintype "passive"))
    )
    (net (code "43") (name "Net-(D6-A)") (class "Default")
      (node (ref "D6") (pin "1") (pinfunction "A_1") (pintype "passive"))
      (node (ref "P4") (pin "1") (pinfunction "1_1") (pintype "passive"))
      (node (ref "Q3") (pin "4") (pinfunction "D_4") (pintype "passive"))
    )
    (net (code "44") (name "Net-(P5-Pad1)") (class "Default")
      (node (ref "P5") (pin "1") (pinfunction "1_1") (pintype "passive"))
      (node (ref "R13") (pin "2") (pinfunction "2_2") (pintype "passive"))
    )
    (net (code "45") (name "Net-(Q1-D)") (class "Default")
      (node (ref "P1") (pin "1") (pinfunction "1_1") (pintype "passive"))
      (node (ref "Q1") (pin "4") (pinfunction "D_4") (pintype "passive"))
    )
    (net (code "46") (name "Net-(Q1-G)") (class "Default")
      (node (ref "Q1") (pin "1") (pinfunction "G_1") (pintype "passive"))
      (node (ref "R1") (pin "2") (pinfunction "2_2") (pintype "passive"))
      (node (ref "U1") (pin "3") (pinfunction "E_3") (pintype "passive"))
    )
    (net (code "47") (name "Net-(Q2-G)") (class "Default")
      (node (ref "Q2") (pin "1") (pinfunction "G_1") (pintype "passive"))
      (node (ref "R7") (pin "2") (pinfunction "2_2") (pintype "passive"))
      (node (ref "U2") (pin "3") (pinfunction "E_3") (pintype "passive"))
    )
    (net (code "48") (name "Net-(Q3-G)") (class "Default")
      (node (ref "Q3") (pin "1") (pinfunction "G_1") (pintype "passive"))
      (node (ref "R9") (pin "2") (pinfunction "2_2") (pintype "passive"))
      (node (ref "U3") (pin "3") (pinfunction "E_3") (pintype "passive"))
    )
    (net (code "49") (name "Net-(Q4-B)") (class "Default")
      (node (ref "Q4") (pin "1") (pinfunction "B_1") (pintype "passive"))
      (node (ref "R14") (pin "1") (pinfunction "1_1") (pintype "passive"))
    )
    (net (code "50") (name "Net-(Q5-B)") (class "Default")
      (node (ref "Q5") (pin "1") (pinfunction "B_1") (pintype "passive"))
      (node (ref "R15") (pin "1") (pinfunction "1_1") (pintype "passive"))
    )
    (net (code "51") (name "Net-(U1-A)") (class "Default")
      (node (ref "R4") (pin "2") (pinfunction "2_2") (pintype "passive"))
      (node (ref "U1") (pin "1") (pinfunction "A_1") (pintype "passive"))
    )
    (net (code "52") (name "Net-(U2-A)") (class "Default")
      (node (ref "R8") (pin "2") (pinfunction "2_2") (pintype "passive"))
      (node (ref "U2") (pin "1") (pinfunction "A_1") (pintype "passive"))
    )
    (net (code "53") (name "Net-(U3-A)") (class "Default")
      (node (ref "R10") (pin "2") (pinfunction "2_2") (pintype "passive"))
      (node (ref "U3") (pin "1") (pinfunction "A_1") (pintype "passive"))
    )
    (net (code "54") (name "Net-(U5-A)") (class "Default")
      (node (ref "R13") (pin "1") (pinfunction "1_1") (pintype "passive"))
      (node (ref "U5") (pin "1") (pinfunction "A_1") (pintype "passive"))
    )
    (net (code "55") (name "Net-(U7-X1)") (class "Default")
      (node (ref "U7") (pin "1") (pinfunction "X1_1") (pintype "input"))
      (node (ref "Y1") (pin "1") (pinfunction "OSC1_1") (pintype "passive"))
    )
    (net (code "56") (name "Net-(U7-X2)") (class "Default")
      (node (ref "U7") (pin "2") (pinfunction "X2_2") (pintype "input"))
      (node (ref "Y1") (pin "2") (pinfunction "OSC2_2") (pintype "passive"))
    )
    (net (code "57") (name "Net-(U8-CVOLT)") (class "Default")
      (node (ref "C10") (pin "2") (pinfunction "2_2") (pintype "passive"))
      (node (ref "U8") (pin "5") (pinfunction "CVOLT_5") (pintype "passive"))
    )
    (net (code "58") (name "Net-(U8-DIS)") (class "Default")
      (node (ref "R27") (pin "2") (pinfunction "2_2") (pintype "passive"))
      (node (ref "R28") (pin "1") (pinfunction "1_1") (pintype "passive"))
      (node (ref "U8") (pin "7") (pinfunction "DIS_7") (pintype "open_collector"))
    )
    (net (code "59") (name "Net-(U8-OUT)") (class "Default")
      (node (ref "R29") (pin "1") (pinfunction "1_1") (pintype "passive"))
      (node (ref "U8") (pin "3") (pinfunction "OUT_3") (pintype "output"))
    )
    (net (code "60") (name "Net-(U8-THR)") (class "Default")
      (node (ref "P11") (pin "1") (pinfunction "1_1") (pintype "passive"))
      (node (ref "R27") (pin "1") (pinfunction "1_1") (pintype "passive"))
      (node (ref "U8") (pin "2") (pinfunction "TRIG_2") (pintype "input"))
      (node (ref "U8") (pin "6") (pinfunction "THR_6") (pintype "input"))
    )
    (net (code "61") (name "unconnected-(CN1-DAT1-Pad8)") (class "Default")
      (node (ref "CN1") (pin "8") (pinfunction "DAT1_8") (pintype "passive+no_connect"))
    )
    (net (code "62") (name "unconnected-(CN1-DAT2-Pad1)") (class "Default")
      (node (ref "CN1") (pin "1") (pinfunction "DAT2_1") (pintype "passive+no_connect"))
    )
    (net (code "63") (name "unconnected-(M1-PadS)") (class "Default")
      (node (ref "M1") (pin "S") (pinfunction "S_S") (pintype "passive"))
    )
    (net (code "64") (name "unconnected-(M2-PadS)") (class "Default")
      (node (ref "M2") (pin "S") (pinfunction "S_S") (pintype "passive"))
    )
    (net (code "65") (name "unconnected-(M3-PadS)") (class "Default")
      (node (ref "M3") (pin "S") (pinfunction "S_S") (pintype "passive"))
    )
    (net (code "66") (name "unconnected-(M4-PadS)") (class "Default")
      (node (ref "M4") (pin "S") (pinfunction "S_S") (pintype "passive"))
    )
    (net (code "67") (name "unconnected-(U4-CLK-Pad20)") (class "Default")
      (node (ref "U4") (pin "20") (pinfunction "CLK_20") (pintype "passive+no_connect"))
    )
    (net (code "68") (name "unconnected-(U4-CMD-Pad19)") (class "Default")
      (node (ref "U4") (pin "19") (pinfunction "CMD_19") (pintype "passive+no_connect"))
    )
    (net (code "69") (name "unconnected-(U4-NC-Pad32)") (class "Default")
      (node (ref "U4") (pin "32") (pinfunction "NC_32") (pintype "passive+no_connect"))
    )
    (net (code "70") (name "unconnected-(U4-SD0-Pad21)") (class "Default")
      (node (ref "U4") (pin "21") (pinfunction "SD0_21") (pintype "passive+no_connect"))
    )
    (net (code "71") (name "unconnected-(U4-SD1-Pad22)") (class "Default")
      (node (ref "U4") (pin "22") (pinfunction "SD1_22") (pintype "passive+no_connect"))
    )
    (net (code "72") (name "unconnected-(U4-SD2-Pad17)") (class "Default")
      (node (ref "U4") (pin "17") (pinfunction "SD2_17") (pintype "passive+no_connect"))
    )
    (net (code "73") (name "unconnected-(U4-SD3-Pad18)") (class "Default")
      (node (ref "U4") (pin "18") (pinfunction "SD3_18") (pintype "passive+no_connect"))
    )
    (net (code "74") (name "unconnected-(U7-SQW{slash}OUT-Pad7)") (class "Default")
      (node (ref "U7") (pin "7") (pinfunction "SQW/OUT_7") (pintype "output"))
    )
  )
)
